# WX0_008_958DL.net
KiCad netlist of a schematic drawn in Altium Designer
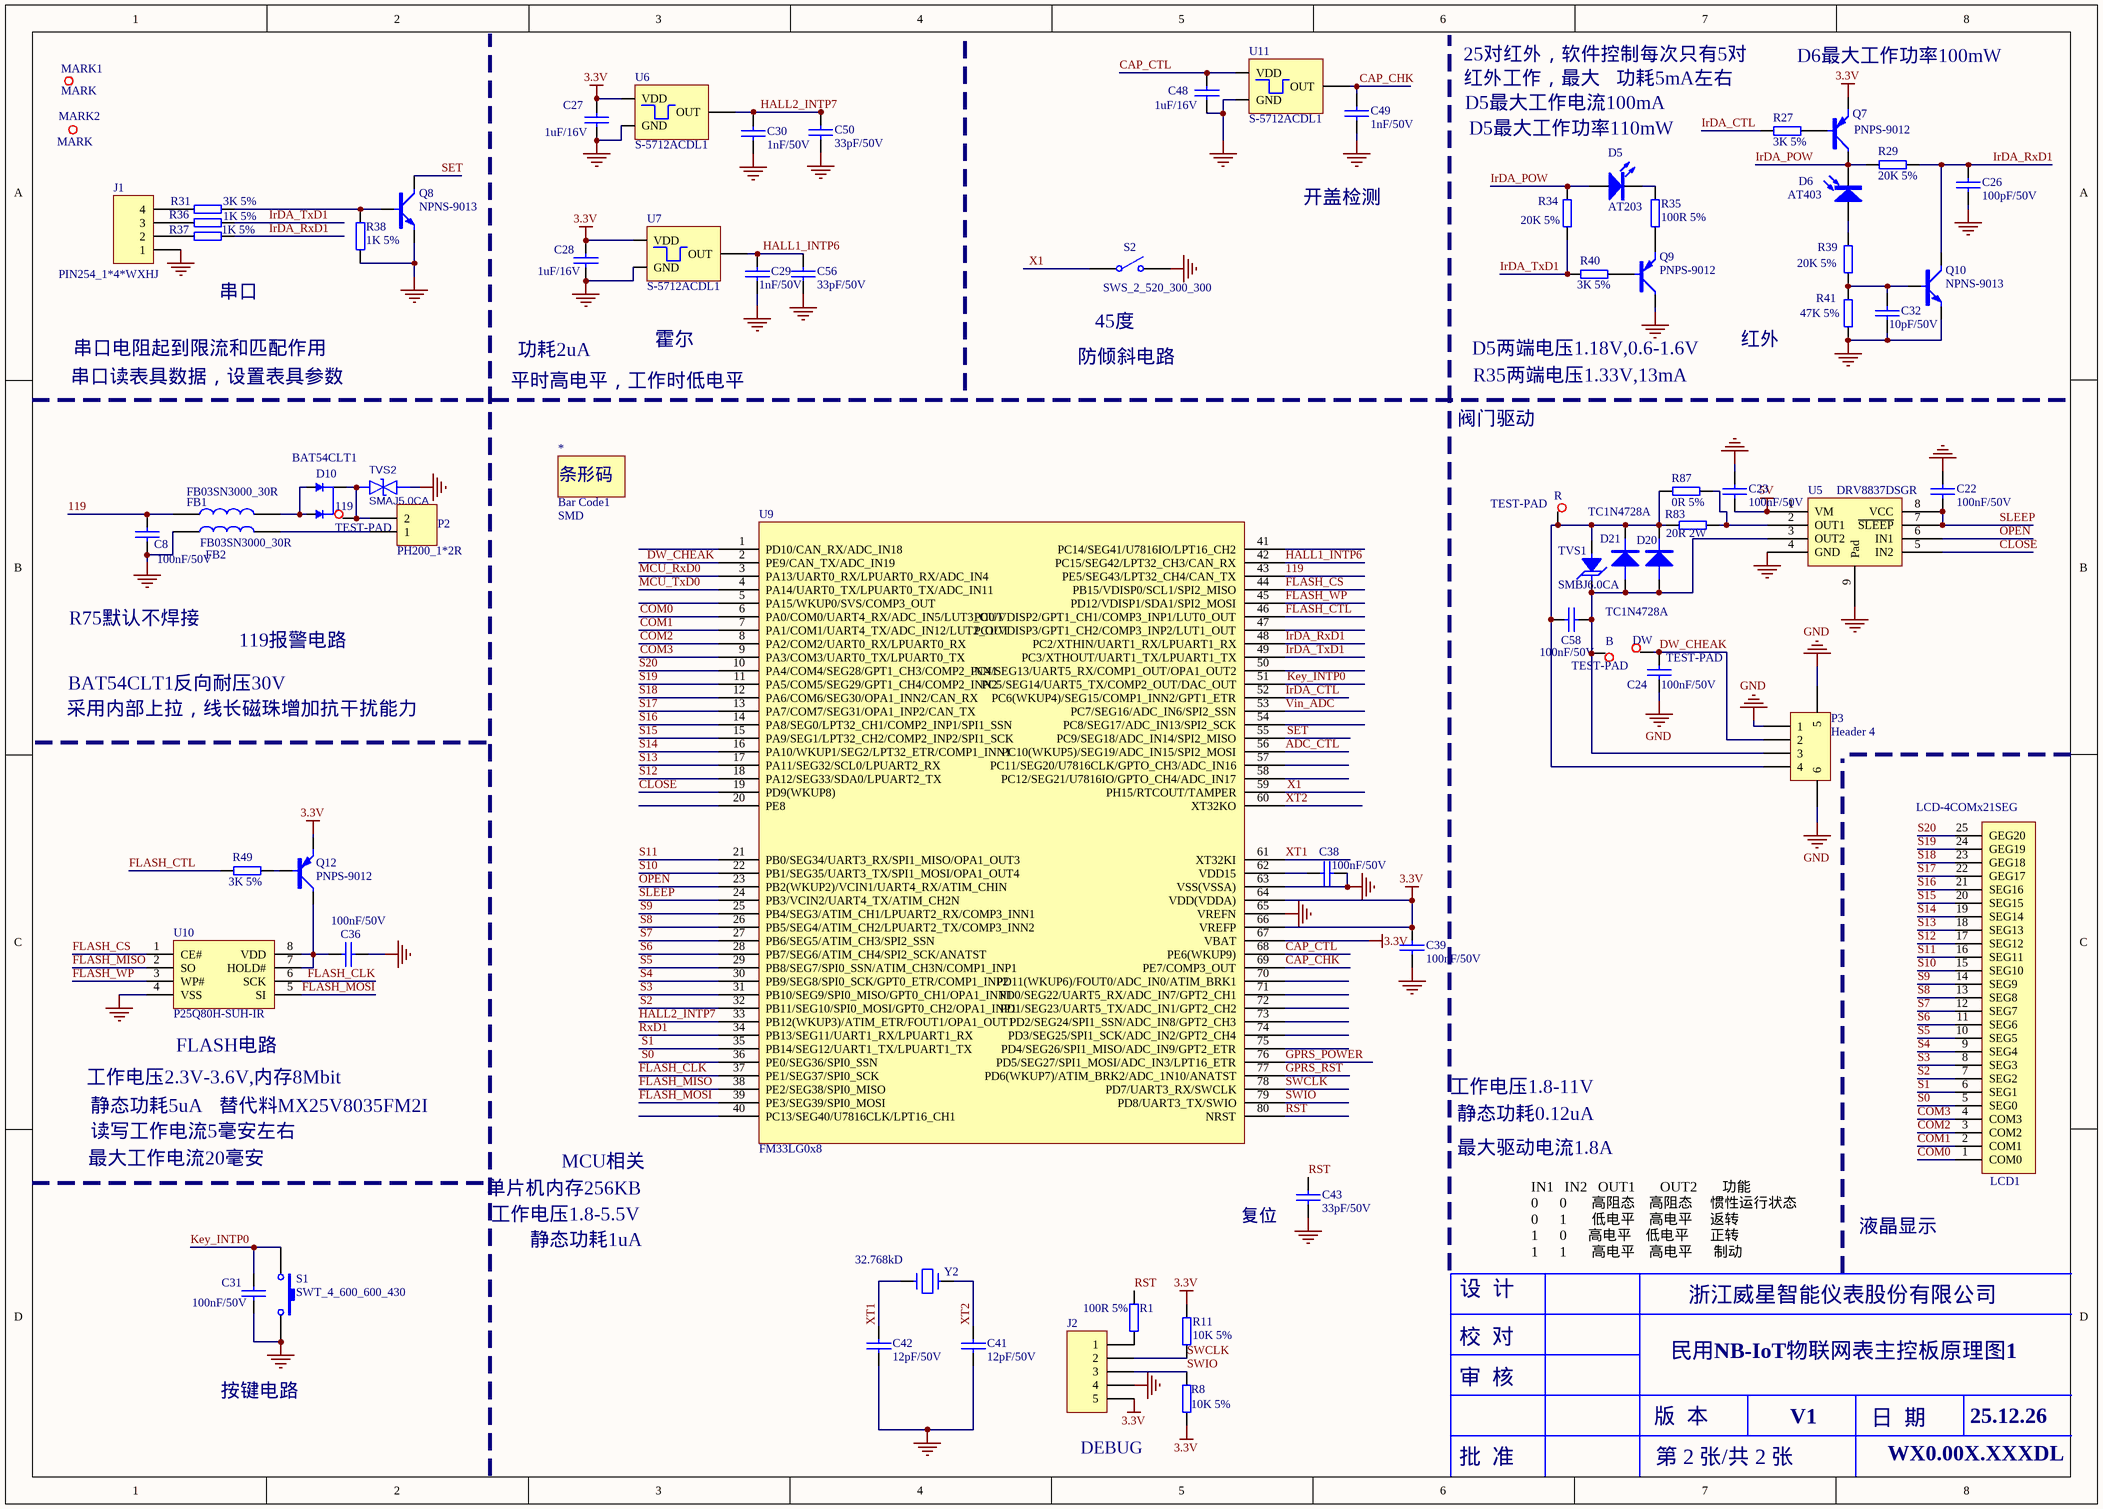
[diagram p0: WX0.008.958DL.SchDoc]

(export (version "E")
  (design (tool "Eeschema 10.0.6"))
  (components
    (comp (ref "*")
      (value "Bar Code1")
      (footprint "Bar Code1")
      (description "条形码 ,填充，无需焊接器件")
      (fields (field (name "PART NUMBER") "AD_WXHJ_Bar Code_02") (field (name "SMD/DIP") "SMD"))
      (libsource (lib "Database_Libs2") (part "05_AD_WXHJ_Bar Code_02"))
    )
    (comp (ref "119")
      (value "TEST-PAD")
      (footprint "TEST-PAD")
      (description "单面焊盘测试点")
      (fields (field (name "PART NUMBER") "AD_WXHJ_TEST-PAD_01"))
      (libsource (lib "Database_Libs2") (part "TEST-PAD"))
    )
    (comp (ref "B")
      (value "TEST-PAD")
      (footprint "TEST-PAD")
      (description "单面焊盘测试点")
      (fields (field (name "PART NUMBER") "AD_WXHJ_TEST-PAD_01"))
      (libsource (lib "Database_Libs2") (part "TEST-PAD"))
    )
    (comp (ref "C8")
      (value "100nF/50V")
      (footprint "CAP0603")
      (description "104pF,50 V,±10%,0603,国巨,CC0603KRX7R9BB104")
      (fields (field (name "PART NUMBER") "101020103-0021"))
      (libsource (lib "Database_Libs2") (part "CC03K7R9_100N"))
    )
    (comp (ref "C22")
      (value "100nF/50V")
      (footprint "CAP0603")
      (description "104pF,50 V,±10%,0603,国巨,CC0603KRX7R9BB104")
      (fields (field (name "PART NUMBER") "101020103-0021"))
      (libsource (lib "Database_Libs2") (part "CC03K7R9_100N"))
    )
    (comp (ref "C23")
      (value "100nF/50V")
      (footprint "CAP0603")
      (description "104pF,50 V,±10%,0603,国巨,CC0603KRX7R9BB104")
      (fields (field (name "PART NUMBER") "101020103-0021"))
      (libsource (lib "Database_Libs2") (part "CC03K7R9_100N"))
    )
    (comp (ref "C24")
      (value "100nF/50V")
      (footprint "CAP0603")
      (description "104pF,50 V,±10%,0603,国巨,CC0603KRX7R9BB104")
      (fields (field (name "PART NUMBER") "101020103-0021"))
      (libsource (lib "Database_Libs2") (part "CC03K7R9_100N"))
    )
    (comp (ref "C26")
      (value "100pF/50V")
      (footprint "CAP0603")
      (description "101pf,50 V,±5%,0603,国巨,CC0603JRNP09BN101")
      (fields (field (name "PART NUMBER") "101020103-0010"))
      (libsource (lib "Database_Libs2") (part "CC03JPO9_101P"))
    )
    (comp (ref "C27")
      (value "1uF/16V")
      (footprint "CAP0603")
      (description "105pF,16 V,±10%,0603,国巨,CC0603KRX7R7BB105")
      (fields (field (name "PART NUMBER") "101020103-0003"))
      (libsource (lib "Database_Libs2") (part "CC03K7R7_1U"))
    )
    (comp (ref "C28")
      (value "1uF/16V")
      (footprint "CAP0603")
      (description "105pF,16 V,±10%,0603,国巨,CC0603KRX7R7BB105")
      (fields (field (name "PART NUMBER") "101020103-0003"))
      (libsource (lib "Database_Libs2") (part "CC03K7R7_1U"))
    )
    (comp (ref "C29")
      (value "1nF/50V")
      (footprint "CAP0603")
      (description "102pF,50 V,±10%,0603,国巨,CC0603KRX7R9BB102")
      (fields (field (name "PART NUMBER") "101020103-0022"))
      (libsource (lib "Database_Libs2") (part "CC03K7R9_1N"))
    )
    (comp (ref "C30")
      (value "1nF/50V")
      (footprint "CAP0603")
      (description "102pF,50 V,±10%,0603,国巨,CC0603KRX7R9BB102")
      (fields (field (name "PART NUMBER") "101020103-0022"))
      (libsource (lib "Database_Libs2") (part "CC03K7R9_1N"))
    )
    (comp (ref "C31")
      (value "100nF/50V")
      (footprint "CAP0603")
      (description "104pF,50 V,±10%,0603,国巨,CC0603KRX7R9BB104")
      (fields (field (name "PART NUMBER") "101020103-0021"))
      (libsource (lib "Database_Libs2") (part "CC03K7R9_100N"))
    )
    (comp (ref "C32")
      (value "10pF/50V")
      (footprint "CAP0603")
      (description "10pF,50 V,±5%,0603,X7R,国巨,CC0603JRNPO9BN100")
      (fields (field (name "PART NUMBER") "101020103-0014"))
      (libsource (lib "Database_Libs2") (part "CC03JPO9_10P"))
    )
    (comp (ref "C36")
      (value "100nF/50V")
      (footprint "CAP0603")
      (description "104pF,50 V,±10%,0603,国巨,CC0603KRX7R9BB104")
      (fields (field (name "PART NUMBER") "101020103-0021"))
      (libsource (lib "Database_Libs2") (part "CC03K7R9_100N"))
    )
    (comp (ref "C38")
      (value "100nF/50V")
      (footprint "CAP0603")
      (description "104pF,50 V,±10%,0603,国巨,CC0603KRX7R9BB104")
      (fields (field (name "PART NUMBER") "101020103-0021"))
      (libsource (lib "Database_Libs2") (part "CC03K7R9_100N"))
    )
    (comp (ref "C39")
      (value "100nF/50V")
      (footprint "CAP0603")
      (description "104pF,50 V,±10%,0603,国巨,CC0603KRX7R9BB104")
      (fields (field (name "PART NUMBER") "101020103-0021"))
      (libsource (lib "Database_Libs2") (part "CC03K7R9_100N"))
    )
    (comp (ref "C41")
      (value "12pF/50V")
      (footprint "CAP0603")
      (description "12P,50 V,±5%,0603,国巨,CC0603JRNPO9BN12")
      (fields (field (name "PART NUMBER") "101020103-0005"))
      (libsource (lib "Database_Libs2") (part "CC03JPO9_12P"))
    )
    (comp (ref "C42")
      (value "12pF/50V")
      (footprint "CAP0603")
      (description "12P,50 V,±5%,0603,国巨,CC0603JRNPO9BN12")
      (fields (field (name "PART NUMBER") "101020103-0005"))
      (libsource (lib "Database_Libs2") (part "CC03JPO9_12P"))
    )
    (comp (ref "C43")
      (value "33pF/50V")
      (footprint "CAP0603")
      (description "33pF,50 V,±10%,0603,国巨,CC0603KRNPO9BN33")
      (fields (field (name "PART NUMBER") "101020103-0027"))
      (libsource (lib "Database_Libs2") (part "CC03KPO9_33P"))
    )
    (comp (ref "C48")
      (value "1uF/16V")
      (footprint "CAP0603")
      (description "105pF,16 V,±10%,0603,国巨,CC0603KRX7R7BB105")
      (fields (field (name "PART NUMBER") "101020103-0003"))
      (libsource (lib "Database_Libs2") (part "CC03K7R7_1U"))
    )
    (comp (ref "C49")
      (value "1nF/50V")
      (footprint "CAP0603")
      (description "102pF,50 V,±10%,0603,国巨,CC0603KRX7R9BB102")
      (fields (field (name "PART NUMBER") "101020103-0022"))
      (libsource (lib "Database_Libs2") (part "CC03K7R9_1N"))
    )
    (comp (ref "C50")
      (value "33pF/50V")
      (footprint "CAP0603")
      (description "33pF,50 V,±10%,0603,国巨,CC0603KRNPO9BN33")
      (fields (field (name "PART NUMBER") "101020103-0027"))
      (libsource (lib "Database_Libs2") (part "CC03KPO9_33P"))
    )
    (comp (ref "C56")
      (value "33pF/50V")
      (footprint "CAP0603")
      (description "33pF,50 V,±10%,0603,国巨,CC0603KRNPO9BN33")
      (fields (field (name "PART NUMBER") "101020103-0027"))
      (libsource (lib "Database_Libs2") (part "CC03KPO9_33P"))
    )
    (comp (ref "C58")
      (value "100nF/50V")
      (footprint "CAP0603")
      (description "104pF,50 V,±10%,0603,国巨,CC0603KRX7R9BB104")
      (fields (field (name "PART NUMBER") "101020103-0021"))
      (libsource (lib "Database_Libs2") (part "CC03K7R9_100N"))
    )
    (comp (ref "D5")
      (value "AT203")
      (footprint "IR_254_532_300")
      (description "DIP-2,φ3,插件,红光,上海品观电子有限公司/可得,AT203")
      (fields (field (name "PART NUMBER") "101040102-0010"))
      (libsource (lib "Database_Libs2") (part "01_AT203"))
    )
    (comp (ref "D6")
      (value "AT403")
      (footprint "IR_254_532_300")
      (description "DIP-2,φ3,插件,红光,上海品观电子有限公司/可得,AT403-PD-01")
      (fields (field (name "PART NUMBER") "101040102-0011"))
      (libsource (lib "Database_Libs2") (part "01_AT403"))
    )
    (comp (ref "D10")
      (value "BAT54CLT1")
      (footprint "SOT-23")
      (description "BAT54CLT1，SOT23-3,SOT23-3,0.2 A,0.8 V,30 V,安森美,BAT54CLT1")
      (fields (field (name "PART NUMBER") "101040101-0038"))
      (libsource (lib "Database_Libs2") (part "02_BAT54CLT1"))
    )
    (comp (ref "D20")
      (value "TC1N4728A")
      (footprint "SOD-123FL")
      (description "4148,4148,0.2 A,1 V,100 V,先科,LL4148")
      (fields (field (name "PART NUMBER") "101040101-0005"))
      (libsource (lib "Database_Libs2") (part "02_LL4148"))
    )
    (comp (ref "D21")
      (value "TC1N4728A")
      (footprint "SOD-123FL")
      (description "4148,4148,0.2 A,1 V,100 V,先科,LL4148")
      (fields (field (name "PART NUMBER") "101040101-0005"))
      (libsource (lib "Database_Libs2") (part "02_LL4148"))
    )
    (comp (ref "DW")
      (value "TEST-PAD")
      (footprint "TEST-PAD")
      (description "单面焊盘测试点")
      (fields (field (name "PART NUMBER") "AD_WXHJ_TEST-PAD_01"))
      (libsource (lib "Database_Libs2") (part "TEST-PAD"))
    )
    (comp (ref "FB1")
      (value "FB03SN3000_30R")
      (footprint "IND0603")
      (description "chilisin(奇力新),0603,30Ω ±25% @100MHz,150 V,125 ℃,PBY160808T-300Y-N,-55 ℃,不含铅,,,圆盘,30Ω ±25% @100MHz")
      (fields (field (name "PART NUMBER") "109010101-0003"))
      (libsource (lib "Database_Libs2") (part "06_FB03SN3000_30R"))
    )
    (comp (ref "FB2")
      (value "FB03SN3000_30R")
      (footprint "IND0603")
      (description "chilisin(奇力新),0603,30Ω ±25% @100MHz,150 V,125 ℃,PBY160808T-300Y-N,-55 ℃,不含铅,,,圆盘,30Ω ±25% @100MHz")
      (fields (field (name "PART NUMBER") "109010101-0003"))
      (libsource (lib "Database_Libs2") (part "06_FB03SN3000_30R"))
    )
    (comp (ref "J1")
      (value "PIN254_1*4*WXHJ")
      (footprint "PIN254_1*4*WXHJ")
      (description "1*4 ，Φ1.0 ，2.54mm，直脚,无需焊接器件")
      (fields (field (name "PART NUMBER") "AD_WXHJ_PinHeader_01"))
      (libsource (lib "Database_Libs2") (part "PIN254_1*4*WXHJ"))
    )
    (comp (ref "J2")
      (value "PIN254_1*5*WXHJ")
      (footprint "PIN254_1*5*WXHJ")
      (description "1*5 ，Φ1.0 ，2.54mm，直脚,无需焊接器件")
      (fields (field (name "PART NUMBER") "AD_WXHJ_PinHeader_02"))
      (libsource (lib "Database_Libs2") (part "PIN254_1*5*WXHJ"))
    )
    (comp (ref "LCD1")
      (value "GVH21861A-HPP")
      (footprint "WX0.008.919PCB-4.1 YUANJIAN:LCD_GVH21861A-HPP")
      (fields (field (name "PART NUMBER") "1010801-0028") (field (name "SMD/DIP") "LCD-4COMx21SEG"))
      (libsource (lib "Database_Libs2") (part "03_LCD_GVH21861A-HPP"))
    )
    (comp (ref "MARK1")
      (value "MARK")
      (footprint "MARK")
      (description "MARK点")
      (fields (field (name "PART NUMBER") "AD_WXHJ_MARK_01"))
      (libsource (lib "Database_Libs2") (part "MARK"))
    )
    (comp (ref "MARK2")
      (value "MARK")
      (footprint "MARK")
      (description "MARK点")
      (fields (field (name "PART NUMBER") "AD_WXHJ_MARK_01"))
      (libsource (lib "Database_Libs2") (part "MARK"))
    )
    (comp (ref "P2")
      (value "PH200_1*2R")
      (footprint "SMT2-2.0")
      (description "2.0-2AW,直插弯座，2PIN，脚间距2mm，带防翘起,公头,单排,2.0-2AW;直插弯座，2PIN,脚间距2mm，带防翘起")
      (fields (field (name "PART NUMBER") "1010902-0105"))
      (libsource (lib "Database_Libs2") (part "PH200_1*2R"))
    )
    (comp (ref "P3")
      (value "Header 4")
      (footprint "WX0.009.048PCB-4.1:SMT-1.25-4")
      (description "Header, 4-Pin")
      (fields (field (name "PUBLISHER") "Altium Limited"))
      (libsource (lib "WX0.000.514") (part "Header 4"))
    )
    (comp (ref "Q7")
      (value "PNPS-9012")
      (footprint "SOT-23")
      (description "9012,PNP,SOT-23,JCET;长电,S9012")
      (fields (field (name "PART NUMBER") "101040201-0001"))
      (libsource (lib "Database_Libs2") (part "03_PNPS-9012"))
    )
    (comp (ref "Q8")
      (value "NPNS-9013")
      (footprint "SOT-23")
      (description "9013,NPN,SOT-23,长电,S9013")
      (fields (field (name "PART NUMBER") "101040201-0002"))
      (libsource (lib "Database_Libs2") (part "03_NPNS-9013"))
    )
    (comp (ref "Q9")
      (value "PNPS-9012")
      (footprint "SOT-23")
      (description "9012,PNP,SOT-23,JCET;长电,S9012")
      (fields (field (name "PART NUMBER") "101040201-0001"))
      (libsource (lib "Database_Libs2") (part "03_PNPS-9012"))
    )
    (comp (ref "Q10")
      (value "NPNS-9013")
      (footprint "SOT-23")
      (description "9013,NPN,SOT-23,长电,S9013")
      (fields (field (name "PART NUMBER") "101040201-0002"))
      (libsource (lib "Database_Libs2") (part "03_NPNS-9013"))
    )
    (comp (ref "Q12")
      (value "PNPS-9012")
      (footprint "SOT-23")
      (description "9012,PNP,SOT-23,JCET;长电,S9012")
      (fields (field (name "PART NUMBER") "101040201-0001"))
      (libsource (lib "Database_Libs2") (part "03_PNPS-9012"))
    )
    (comp (ref "R")
      (value "TEST-PAD")
      (footprint "TEST-PAD")
      (description "单面焊盘测试点")
      (fields (field (name "PART NUMBER") "AD_WXHJ_TEST-PAD_01"))
      (libsource (lib "Database_Libs2") (part "TEST-PAD"))
    )
    (comp (ref "R1")
      (value "100R 5%")
      (footprint "RES0603")
      (description "100R,±5%,1/10W,0603,国巨,RC0603JR-07100RL")
      (fields (field (name "PART NUMBER") "101010103-0022"))
      (libsource (lib "Database_Libs2") (part "RC03J_100R"))
    )
    (comp (ref "R8")
      (value "10K 5%")
      (footprint "RES0603")
      (description "国巨,±5%,0603,,155 ℃,-55 ℃,RC0603JR-0710KL,无铅,200 ppm/℃,1/10W,,10K")
      (fields (field (name "PART NUMBER") "101010103-0003"))
      (libsource (lib "Database_Libs2") (part "RC03J_10K"))
    )
    (comp (ref "R11")
      (value "10K 5%")
      (footprint "RES0603")
      (description "国巨,±5%,0603,,155 ℃,-55 ℃,RC0603JR-0710KL,无铅,200 ppm/℃,1/10W,,10K")
      (fields (field (name "PART NUMBER") "101010103-0003"))
      (libsource (lib "Database_Libs2") (part "RC03J_10K"))
    )
    (comp (ref "R27")
      (value "3K 5%")
      (footprint "RES0603")
      (description "国巨,±5%,0603,,155 ℃,-55 ℃,RC0603JR-073KL,无铅,100 ppm/℃,1/10W,,3K")
      (fields (field (name "PART NUMBER") "101010103-0006"))
      (libsource (lib "Database_Libs2") (part "RC03J_3K"))
    )
    (comp (ref "R29")
      (value "20K 5%")
      (footprint "RES0603")
      (description "国巨,±5%,0603,,155 ℃,-55 ℃,RC0603JR-0720KL,无铅,200 ppm/℃,1/10W,,20K")
      (fields (field (name "PART NUMBER") "101010103-0004"))
      (libsource (lib "Database_Libs2") (part "RC03J_20K"))
    )
    (comp (ref "R31")
      (value "3K 5%")
      (footprint "RES0603")
      (description "国巨,±5%,0603,,155 ℃,-55 ℃,RC0603JR-073KL,无铅,100 ppm/℃,1/10W,,3K")
      (fields (field (name "PART NUMBER") "101010103-0006"))
      (libsource (lib "Database_Libs2") (part "RC03J_3K"))
    )
    (comp (ref "R34")
      (value "20K 5%")
      (footprint "RES0603")
      (description "国巨,±5%,0603,,155 ℃,-55 ℃,RC0603JR-0720KL,无铅,200 ppm/℃,1/10W,,20K")
      (fields (field (name "PART NUMBER") "101010103-0004"))
      (libsource (lib "Database_Libs2") (part "RC03J_20K"))
    )
    (comp (ref "R35")
      (value "100R 5%")
      (footprint "RES0603")
      (description "100R,±5%,1/10W,0603,国巨,RC0603JR-07100RL")
      (fields (field (name "PART NUMBER") "101010103-0022"))
      (libsource (lib "Database_Libs2") (part "RC03J_100R"))
    )
    (comp (ref "R36")
      (value "1K 5%")
      (footprint "RES0603")
      (description "1K,±5%,1/10W,0603,国巨,RC0603JR-071KL")
      (fields (field (name "PART NUMBER") "101010103-0008"))
      (libsource (lib "Database_Libs2") (part "RC03J_1K"))
    )
    (comp (ref "R37")
      (value "1K 5%")
      (footprint "RES0603")
      (description "1K,±5%,1/10W,0603,国巨,RC0603JR-071KL")
      (fields (field (name "PART NUMBER") "101010103-0008"))
      (libsource (lib "Database_Libs2") (part "RC03J_1K"))
    )
    (comp (ref "R38")
      (value "1K 5%")
      (footprint "RES0603")
      (description "1K,±5%,1/10W,0603,国巨,RC0603JR-071KL")
      (fields (field (name "PART NUMBER") "101010103-0008"))
      (libsource (lib "Database_Libs2") (part "RC03J_1K"))
    )
    (comp (ref "R39")
      (value "20K 5%")
      (footprint "RES0603")
      (description "国巨,±5%,0603,,155 ℃,-55 ℃,RC0603JR-0720KL,无铅,200 ppm/℃,1/10W,,20K")
      (fields (field (name "PART NUMBER") "101010103-0004"))
      (libsource (lib "Database_Libs2") (part "RC03J_20K"))
    )
    (comp (ref "R40")
      (value "3K 5%")
      (footprint "RES0603")
      (description "国巨,±5%,0603,,155 ℃,-55 ℃,RC0603JR-073KL,无铅,100 ppm/℃,1/10W,,3K")
      (fields (field (name "PART NUMBER") "101010103-0006"))
      (libsource (lib "Database_Libs2") (part "RC03J_3K"))
    )
    (comp (ref "R41")
      (value "47K 5%")
      (footprint "RES0603")
      (description "47K,±5%,1/10W,0603,国巨,RC0603JR-0747KL")
      (fields (field (name "PART NUMBER") "101010103-0012"))
      (libsource (lib "Database_Libs2") (part "RC03J_47K"))
    )
    (comp (ref "R49")
      (value "3K 5%")
      (footprint "RES0603")
      (description "国巨,±5%,0603,,155 ℃,-55 ℃,RC0603JR-073KL,无铅,100 ppm/℃,1/10W,,3K")
      (fields (field (name "PART NUMBER") "101010103-0006"))
      (libsource (lib "Database_Libs2") (part "RC03J_3K"))
    )
    (comp (ref "R83")
      (value "20R 2W")
      (footprint "金属膜电阻")
      (description "国巨,±5%,0603,,155 ℃,-55 ℃,RC0603JR-0722RL,无铅,200 ppm/℃,1/10W,,22欧")
      (fields (field (name "PART NUMBER") "101010103-0009"))
      (libsource (lib "Database_Libs2") (part "RC03J_22R"))
    )
    (comp (ref "R87")
      (value "0R 5%")
      (footprint "RES1206")
      (description "0Ω,±5%,1/4W,1206,国巨,RC1206JR-070RL")
      (fields (field (name "PART NUMBER") "101010101-0013"))
      (libsource (lib "Database_Libs2") (part "RC06J_0R"))
    )
    (comp (ref "S1")
      (value "SWT_4_600_600_430")
      (footprint "SWT_4_600_600")
      (description "TS-1102,机械轻触,6*6*4.3直插,6*6*4.3直插,乐清市羽欧电子")
      (fields (field (name "PART NUMBER") "1011001-0027"))
      (libsource (lib "Database_Libs2") (part "07_SWT_4_600_600_430"))
    )
    (comp (ref "S2")
      (value "SWS_2_520_300_300")
      (footprint "Discrete_WX:SWS_2_520_300")
      (description "CSX-SEN-645B,垂直45°开关转换,3*5.2mm,360°任意方位倾斜检测,深圳市成晟科技有限公司")
      (fields (field (name "PART NUMBER") "1011001-0051"))
      (libsource (lib "Database_Libs2") (part "07_SWS_2_520_300_300"))
    )
    (comp (ref "TVS1")
      (value "SMBJ6.0CA")
      (footprint "DO-214AA")
      (description "SMBJ6.0CA,DO-214AA,10.3 V,6.0 V,600 W,58.3 A,800 uA,上海君耀电子有限公司,SMBJ6.0CA")
      (fields (field (name "PART NUMBER") "101040101-0024"))
      (libsource (lib "Database_Libs2") (part "05_SMBJ6.0CA"))
    )
    (comp (ref "TVS2")
      (value "SMAJ5.0CA")
      (footprint "SMAJ5.0CA")
      (fields (field (name "BOM_SUPPLIER PART") "C693487") (field (name "CONTRIBUTOR") "LCSC"))
      (libsource (lib "Discrete_WX") (part "SMAJ5.0CA_C693487"))
    )
    (comp (ref "U5")
      (value "DRV8837DSGR")
      (footprint "S-PWSON-N8")
      (description "DRV8837DSGR,S-PWSON-N8,TI,DRV8837DSGR")
      (fields (field (name "PART NUMBER") "101050101-0060"))
      (libsource (lib "Database_Libs2") (part "07_DRV8837DSGR"))
    )
    (comp (ref "U6")
      (value "S-5712ACDL1")
      (footprint "SOT-23")
      (description "S-5712ACDL1,SOT23-3,3.5 V,1.6 V,2 uA,精工电子,S-5712ACDL1")
      (fields (field (name "PART NUMBER") "1010504-0002"))
      (libsource (lib "Database_Libs2") (part "01_S-5712ACDL1"))
    )
    (comp (ref "U7")
      (value "S-5712ACDL1")
      (footprint "SOT-23")
      (description "S-5712ACDL1,SOT23-3,3.5 V,1.6 V,2 uA,精工电子,S-5712ACDL1")
      (fields (field (name "PART NUMBER") "1010504-0002"))
      (libsource (lib "Database_Libs2") (part "01_S-5712ACDL1"))
    )
    (comp (ref "U9")
      (value "FM33LG0x8")
      (footprint "Chip_WX:LQFP80")
      (libsource (lib "FM_MCU") (part "FM33LG0x8"))
    )
    (comp (ref "U10")
      (value "P25Q80H-SUH-IR")
      (footprint "SOP-8L-200MIL")
      (description "P25Q80H-SUH-IR,SOP8208mil,普冉半导体（上海）股份有限公司,P25Q80H-SUH-IR")
      (fields (field (name "PART NUMBER") "101050101-0218"))
      (libsource (lib "Database_Libs2") (part "04_GD25VQ80CSIG"))
    )
    (comp (ref "U11")
      (value "S-5712ACDL1")
      (footprint "SOT-23")
      (description "S-5712ACDL1,SOT23-3,3.5 V,1.6 V,2 uA,精工电子,S-5712ACDL1")
      (fields (field (name "PART NUMBER") "1010504-0002"))
      (libsource (lib "Database_Libs2") (part "01_S-5712ACDL1"))
    )
    (comp (ref "Y2")
      (value "32.768kD")
      (footprint "SMD-3215_2P")
      (fields (field (name "PART NUMBER") "1010601-0020"))
      (libsource (lib "Database_Libs2") (part "04_XTALSG12MD_32.768kD"))
    )
  )
  (nets
    (net (code "1") (name "/119") (class "Default")
      (node (ref "C8") (pin "1") (pinfunction "1_1") (pintype "passive"))
      (node (ref "FB1") (pin "1") (pinfunction "1_1") (pintype "passive"))
      (node (ref "U9") (pin "43") (pinfunction "PE5/SEG43/LPT32_CH4/CAN_TX_43") (pintype "passive"))
    )
    (net (code "2") (name "/ADC_CTL") (class "Default")
      (node (ref "U9") (pin "56") (pinfunction "PC10(WKUP5)/SEG19/ADC_IN15/SPI2_MOSI_56") (pintype "passive"))
    )
    (net (code "3") (name "/CAP_CHK") (class "Default")
      (node (ref "C49") (pin "1") (pinfunction "1_1") (pintype "passive"))
      (node (ref "U11") (pin "2") (pinfunction "OUT_2") (pintype "passive"))
      (node (ref "U9") (pin "69") (pinfunction "PE7/COMP3_OUT_69") (pintype "passive"))
    )
    (net (code "4") (name "/CAP_CTL") (class "Default")
      (node (ref "C48") (pin "1") (pinfunction "1_1") (pintype "passive"))
      (node (ref "U11") (pin "1") (pinfunction "VDD_1") (pintype "passive"))
      (node (ref "U9") (pin "68") (pinfunction "PE6(WKUP9)_68") (pintype "passive"))
    )
    (net (code "5") (name "/CLOSE") (class "Default")
      (node (ref "U5") (pin "5") (pinfunction "IN2_5") (pintype "passive"))
      (node (ref "U9") (pin "19") (pinfunction "PD9(WKUP8)_19") (pintype "passive"))
    )
    (net (code "6") (name "/COM0") (class "Default")
      (node (ref "LCD1") (pin "1") (pinfunction "COM0_1") (pintype "passive"))
      (node (ref "U9") (pin "6") (pinfunction "PA0/COM0/UART4_RX/ADC_IN5/LUT3_OUT_6") (pintype "passive"))
    )
    (net (code "7") (name "/COM1") (class "Default")
      (node (ref "LCD1") (pin "2") (pinfunction "COM1_2") (pintype "passive"))
      (node (ref "U9") (pin "7") (pinfunction "PA1/COM1/UART4_TX/ADC_IN12/LUT2_OUT_7") (pintype "passive"))
    )
    (net (code "8") (name "/COM2") (class "Default")
      (node (ref "LCD1") (pin "3") (pinfunction "COM2_3") (pintype "passive"))
      (node (ref "U9") (pin "8") (pinfunction "PA2/COM2/UART0_RX/LPUART0_RX_8") (pintype "passive"))
    )
    (net (code "9") (name "/COM3") (class "Default")
      (node (ref "LCD1") (pin "4") (pinfunction "COM3_4") (pintype "passive"))
      (node (ref "U9") (pin "9") (pinfunction "PA3/COM3/UART0_TX/LPUART0_TX_9") (pintype "passive"))
    )
    (net (code "10") (name "/DW_CHEAK") (class "Default")
      (node (ref "C24") (pin "1") (pinfunction "1_1") (pintype "passive"))
      (node (ref "DW") (pin "1") (pinfunction "1_1") (pintype "passive"))
      (node (ref "P3") (pin "2") (pinfunction "2_2") (pintype "passive"))
      (node (ref "U9") (pin "2") (pinfunction "PE9/CAN_TX/ADC_IN19_2") (pintype "passive"))
    )
    (net (code "11") (name "/FLASH_CLK") (class "Default")
      (node (ref "U10") (pin "6") (pinfunction "SCK_6") (pintype "passive"))
      (node (ref "U9") (pin "37") (pinfunction "PE1/SEG37/SPI0_SCK_37") (pintype "passive"))
    )
    (net (code "12") (name "/FLASH_CS") (class "Default")
      (node (ref "U10") (pin "1") (pinfunction "CE#_1") (pintype "passive"))
      (node (ref "U9") (pin "44") (pinfunction "PB15/VDISP0/SCL1/SPI2_MISO_44") (pintype "passive"))
    )
    (net (code "13") (name "/FLASH_CTL") (class "Default")
      (node (ref "R49") (pin "1") (pinfunction "1_1") (pintype "passive"))
      (node (ref "U9") (pin "46") (pinfunction "PC0/VDISP2/GPT1_CH1/COMP3_INP1/LUT0_OUT_46") (pintype "passive"))
    )
    (net (code "14") (name "/FLASH_MISO") (class "Default")
      (node (ref "U10") (pin "2") (pinfunction "SO_2") (pintype "passive"))
      (node (ref "U9") (pin "38") (pinfunction "PE2/SEG38/SPI0_MISO_38") (pintype "passive"))
    )
    (net (code "15") (name "/FLASH_MOSI") (class "Default")
      (node (ref "U10") (pin "5") (pinfunction "SI_5") (pintype "passive"))
      (node (ref "U9") (pin "39") (pinfunction "PE3/SEG39/SPI0_MOSI_39") (pintype "passive"))
    )
    (net (code "16") (name "/FLASH_WP") (class "Default")
      (node (ref "U10") (pin "3") (pinfunction "WP#_3") (pintype "passive"))
      (node (ref "U9") (pin "45") (pinfunction "PD12/VDISP1/SDA1/SPI2_MOSI_45") (pintype "passive"))
    )
    (net (code "17") (name "/GPRS_POWER") (class "Default")
      (node (ref "U9") (pin "76") (pinfunction "PD5/SEG27/SPI1_MOSI/ADC_IN3/LPT16_ETR_76") (pintype "passive"))
    )
    (net (code "18") (name "/GPRS_RST") (class "Default")
      (node (ref "U9") (pin "77") (pinfunction "PD6(WKUP7)/ATIM_BRK2/ADC_1N10/ANATST_77") (pintype "passive"))
    )
    (net (code "19") (name "/HALL1_INTP6") (class "Default")
      (node (ref "C29") (pin "1") (pinfunction "1_1") (pintype "passive"))
      (node (ref "C56") (pin "1") (pinfunction "1_1") (pintype "passive"))
      (node (ref "U7") (pin "2") (pinfunction "OUT_2") (pintype "passive"))
      (node (ref "U9") (pin "42") (pinfunction "PC15/SEG42/LPT32_CH3/CAN_RX_42") (pintype "passive"))
    )
    (net (code "20") (name "/HALL2_INTP7") (class "Default")
      (node (ref "C30") (pin "1") (pinfunction "1_1") (pintype "passive"))
      (node (ref "C50") (pin "1") (pinfunction "1_1") (pintype "passive"))
      (node (ref "U6") (pin "2") (pinfunction "OUT_2") (pintype "passive"))
      (node (ref "U9") (pin "33") (pinfunction "PB12(WKUP3)/ATIM_ETR/FOUT1/OPA1_OUT1_33") (pintype "passive"))
    )
    (net (code "21") (name "/IrDA_CTL") (class "Default")
      (node (ref "R27") (pin "1") (pinfunction "1_1") (pintype "passive"))
      (node (ref "U9") (pin "52") (pinfunction "PC6(WKUP4)/SEG15/COMP1_INN2/GPT1_ETR_52") (pintype "passive"))
    )
    (net (code "22") (name "/IrDA_POW") (class "Default")
      (node (ref "D5") (pin "1") (pinfunction "A_1") (pintype "passive"))
      (node (ref "D6") (pin "2") (pinfunction "K_2") (pintype "passive"))
      (node (ref "Q7") (pin "3") (pinfunction "C_3") (pintype "passive"))
      (node (ref "R29") (pin "1") (pinfunction "1_1") (pintype "passive"))
      (node (ref "R34") (pin "2") (pinfunction "2_2") (pintype "passive"))
    )
    (net (code "23") (name "/IrDA_RxD1") (class "Default")
      (node (ref "C26") (pin "1") (pinfunction "1_1") (pintype "passive"))
      (node (ref "Q10") (pin "3") (pinfunction "C_3") (pintype "passive"))
      (node (ref "R29") (pin "2") (pinfunction "2_2") (pintype "passive"))
      (node (ref "R37") (pin "2") (pinfunction "2_2") (pintype "passive"))
      (node (ref "U9") (pin "48") (pinfunction "PC2/XTHIN/UART1_RX/LPUART1_RX_48") (pintype "passive"))
    )
    (net (code "24") (name "/IrDA_TxD1") (class "Default")
      (node (ref "R34") (pin "1") (pinfunction "1_1") (pintype "passive"))
      (node (ref "R36") (pin "2") (pinfunction "2_2") (pintype "passive"))
      (node (ref "R40") (pin "1") (pinfunction "1_1") (pintype "passive"))
      (node (ref "U9") (pin "49") (pinfunction "PC3/XTHOUT/UART1_TX/LPUART1_TX_49") (pintype "passive"))
    )
    (net (code "25") (name "/Key_INTP0") (class "Default")
      (node (ref "C31") (pin "1") (pinfunction "1_1") (pintype "passive"))
      (node (ref "S1") (pin "1") (pinfunction "1_1") (pintype "passive"))
      (node (ref "U9") (pin "51") (pinfunction "PC5/SEG14/UART5_TX/COMP2_OUT/DAC_OUT_51") (pintype "passive"))
    )
    (net (code "26") (name "/MCU_RxD0") (class "Default")
      (node (ref "U9") (pin "3") (pinfunction "PA13/UART0_RX/LPUART0_RX/ADC_IN4_3") (pintype "passive"))
    )
    (net (code "27") (name "/MCU_TxD0") (class "Default")
      (node (ref "U9") (pin "4") (pinfunction "PA14/UART0_TX/LPUART0_TX/ADC_IN11_4") (pintype "passive"))
    )
    (net (code "28") (name "/OPEN") (class "Default")
      (node (ref "U5") (pin "6") (pinfunction "IN1_6") (pintype "passive"))
      (node (ref "U9") (pin "23") (pinfunction "PB2(WKUP2)/VCIN1/UART4_RX/ATIM_CHIN_23") (pintype "passive"))
    )
    (net (code "29") (name "/RST") (class "Default")
      (node (ref "C43") (pin "1") (pinfunction "1_1") (pintype "passive"))
      (node (ref "R1") (pin "1") (pinfunction "1_1") (pintype "passive"))
      (node (ref "U9") (pin "80") (pinfunction "NRST_80") (pintype "passive"))
    )
    (net (code "30") (name "/RxD1") (class "Default")
      (node (ref "U9") (pin "34") (pinfunction "PB13/SEG11/UART1_RX/LPUART1_RX_34") (pintype "passive"))
    )
    (net (code "31") (name "/S0") (class "Default")
      (node (ref "LCD1") (pin "5") (pinfunction "SEG0_5") (pintype "passive"))
      (node (ref "U9") (pin "36") (pinfunction "PE0/SEG36/SPI0_SSN_36") (pintype "passive"))
    )
    (net (code "32") (name "/S1") (class "Default")
      (node (ref "LCD1") (pin "6") (pinfunction "SEG1_6") (pintype "passive"))
      (node (ref "U9") (pin "35") (pinfunction "PB14/SEG12/UART1_TX/LPUART1_TX_35") (pintype "passive"))
    )
    (net (code "33") (name "/S2") (class "Default")
      (node (ref "LCD1") (pin "7") (pinfunction "SEG2_7") (pintype "passive"))
      (node (ref "U9") (pin "32") (pinfunction "PB11/SEG10/SPI0_MOSI/GPT0_CH2/OPA1_INP1_32") (pintype "passive"))
    )
    (net (code "34") (name "/S3") (class "Default")
      (node (ref "LCD1") (pin "8") (pinfunction "SEG3_8") (pintype "passive"))
      (node (ref "U9") (pin "31") (pinfunction "PB10/SEG9/SPI0_MISO/GPT0_CH1/OPA1_INN1_31") (pintype "passive"))
    )
    (net (code "35") (name "/S4") (class "Default")
      (node (ref "LCD1") (pin "9") (pinfunction "SEG4_9") (pintype "passive"))
      (node (ref "U9") (pin "30") (pinfunction "PB9/SEG8/SPI0_SCK/GPT0_ETR/COMP1_INP2_30") (pintype "passive"))
    )
    (net (code "36") (name "/S5") (class "Default")
      (node (ref "LCD1") (pin "10") (pinfunction "SEG5_10") (pintype "passive"))
      (node (ref "U9") (pin "29") (pinfunction "PB8/SEG7/SPI0_SSN/ATIM_CH3N/COMP1_INP1_29") (pintype "passive"))
    )
    (net (code "37") (name "/S6") (class "Default")
      (node (ref "LCD1") (pin "11") (pinfunction "SEG6_11") (pintype "passive"))
      (node (ref "U9") (pin "28") (pinfunction "PB7/SEG6/ATIM_CH4/SPI2_SCK/ANATST_28") (pintype "passive"))
    )
    (net (code "38") (name "/S7") (class "Default")
      (node (ref "LCD1") (pin "12") (pinfunction "SEG7_12") (pintype "passive"))
      (node (ref "U9") (pin "27") (pinfunction "PB6/SEG5/ATIM_CH3/SPI2_SSN_27") (pintype "passive"))
    )
    (net (code "39") (name "/S8") (class "Default")
      (node (ref "LCD1") (pin "13") (pinfunction "SEG8_13") (pintype "passive"))
      (node (ref "U9") (pin "26") (pinfunction "PB5/SEG4/ATIM_CH2/LPUART2_TX/COMP3_INN2_26") (pintype "passive"))
    )
    (net (code "40") (name "/S9") (class "Default")
      (node (ref "LCD1") (pin "14") (pinfunction "SEG9_14") (pintype "passive"))
      (node (ref "U9") (pin "25") (pinfunction "PB4/SEG3/ATIM_CH1/LPUART2_RX/COMP3_INN1_25") (pintype "passive"))
    )
    (net (code "41") (name "/S10") (class "Default")
      (node (ref "LCD1") (pin "15") (pinfunction "SEG10_15") (pintype "passive"))
      (node (ref "U9") (pin "22") (pinfunction "PB1/SEG35/UART3_TX/SPI1_MOSI/OPA1_OUT4_22") (pintype "passive"))
    )
    (net (code "42") (name "/S11") (class "Default")
      (node (ref "LCD1") (pin "16") (pinfunction "SEG11_16") (pintype "passive"))
      (node (ref "U9") (pin "21") (pinfunction "PB0/SEG34/UART3_RX/SPI1_MISO/OPA1_OUT3_21") (pintype "passive"))
    )
    (net (code "43") (name "/S12") (class "Default")
      (node (ref "LCD1") (pin "17") (pinfunction "SEG12_17") (pintype "passive"))
      (node (ref "U9") (pin "18") (pinfunction "PA12/SEG33/SDA0/LPUART2_TX_18") (pintype "passive"))
    )
    (net (code "44") (name "/S13") (class "Default")
      (node (ref "LCD1") (pin "18") (pinfunction "SEG13_18") (pintype "passive"))
      (node (ref "U9") (pin "17") (pinfunction "PA11/SEG32/SCL0/LPUART2_RX_17") (pintype "passive"))
    )
    (net (code "45") (name "/S14") (class "Default")
      (node (ref "LCD1") (pin "19") (pinfunction "SEG14_19") (pintype "passive"))
      (node (ref "U9") (pin "16") (pinfunction "PA10/WKUP1/SEG2/LPT32_ETR/COMP1_INN1_16") (pintype "passive"))
    )
    (net (code "46") (name "/S15") (class "Default")
      (node (ref "LCD1") (pin "20") (pinfunction "SEG15_20") (pintype "passive"))
      (node (ref "U9") (pin "15") (pinfunction "PA9/SEG1/LPT32_CH2/COMP2_INP2/SPI1_SCK_15") (pintype "passive"))
    )
    (net (code "47") (name "/S16") (class "Default")
      (node (ref "LCD1") (pin "21") (pinfunction "SEG16_21") (pintype "passive"))
      (node (ref "U9") (pin "14") (pinfunction "PA8/SEG0/LPT32_CH1/COMP2_INP1/SPI1_SSN_14") (pintype "passive"))
    )
    (net (code "48") (name "/S17") (class "Default")
      (node (ref "LCD1") (pin "22") (pinfunction "GEG17_22") (pintype "passive"))
      (node (ref "U9") (pin "13") (pinfunction "PA7/COM7/SEG31/OPA1_INP2/CAN_TX_13") (pintype "passive"))
    )
    (net (code "49") (name "/S18") (class "Default")
      (node (ref "LCD1") (pin "23") (pinfunction "GEG18_23") (pintype "passive"))
      (node (ref "U9") (pin "12") (pinfunction "PA6/COM6/SEG30/OPA1_INN2/CAN_RX_12") (pintype "passive"))
    )
    (net (code "50") (name "/S19") (class "Default")
      (node (ref "LCD1") (pin "24") (pinfunction "GEG19_24") (pintype "passive"))
      (node (ref "U9") (pin "11") (pinfunction "PA5/COM5/SEG29/GPT1_CH4/COMP2_INN2_11") (pintype "passive"))
    )
    (net (code "51") (name "/S20") (class "Default")
      (node (ref "LCD1") (pin "25") (pinfunction "GEG20_25") (pintype "passive"))
      (node (ref "U9") (pin "10") (pinfunction "PA4/COM4/SEG28/GPT1_CH3/COMP2_INN1_10") (pintype "passive"))
    )
    (net (code "52") (name "/SET") (class "Default")
      (node (ref "Q8") (pin "3") (pinfunction "C_3") (pintype "passive"))
      (node (ref "U9") (pin "55") (pinfunction "PC9/SEG18/ADC_IN14/SPI2_MISO_55") (pintype "passive"))
    )
    (net (code "53") (name "/SLEEP") (class "Default")
      (node (ref "C22") (pin "2") (pinfunction "2_2") (pintype "passive"))
      (node (ref "U5") (pin "7") (pinfunction "~{SLEEP}_7") (pintype "passive"))
      (node (ref "U5") (pin "8") (pinfunction "VCC_8") (pintype "passive"))
      (node (ref "U9") (pin "24") (pinfunction "PB3/VCIN2/UART4_TX/ATIM_CH2N_24") (pintype "passive"))
    )
    (net (code "54") (name "/SWCLK") (class "Default")
      (node (ref "J2") (pin "2") (pinfunction "2_2") (pintype "passive"))
      (node (ref "R11") (pin "2") (pinfunction "2_2") (pintype "passive"))
      (node (ref "U9") (pin "78") (pinfunction "PD7/UART3_RX/SWCLK_78") (pintype "passive"))
    )
    (net (code "55") (name "/SWIO") (class "Default")
      (node (ref "J2") (pin "3") (pinfunction "3_3") (pintype "passive"))
      (node (ref "R8") (pin "2") (pinfunction "2_2") (pintype "passive"))
      (node (ref "U9") (pin "79") (pinfunction "PD8/UART3_TX/SWIO_79") (pintype "passive"))
    )
    (net (code "56") (name "/Vin_ADC") (class "Default")
      (node (ref "U9") (pin "53") (pinfunction "PC7/SEG16/ADC_IN6/SPI2_SSN_53") (pintype "passive"))
    )
    (net (code "57") (name "/X1") (class "Default")
      (node (ref "S2") (pin "1") (pintype "passive"))
      (node (ref "U9") (pin "59") (pinfunction "PH15/RTCOUT/TAMPER_59") (pintype "passive"))
    )
    (net (code "58") (name "/XT1") (class "Default")
      (node (ref "C42") (pin "1") (pinfunction "1_1") (pintype "passive"))
      (node (ref "U9") (pin "61") (pinfunction "XT32KI_61") (pintype "passive"))
      (node (ref "Y2") (pin "1") (pinfunction "1_1") (pintype "passive"))
    )
    (net (code "59") (name "/XT2") (class "Default")
      (node (ref "C41") (pin "2") (pinfunction "2_2") (pintype "passive"))
      (node (ref "U9") (pin "60") (pinfunction "XT32KO_60") (pintype "passive"))
      (node (ref "Y2") (pin "2") (pinfunction "2_2") (pintype "passive"))
    )
    (net (code "60") (name "3.3V") (class "Default")
      (node (ref "C27") (pin "1") (pinfunction "1_1") (pintype "passive"))
      (node (ref "C28") (pin "1") (pinfunction "1_1") (pintype "passive"))
      (node (ref "C39") (pin "2") (pinfunction "2_2") (pintype "passive"))
      (node (ref "J2") (pin "5") (pinfunction "5_5") (pintype "passive"))
      (node (ref "Q12") (pin "2") (pinfunction "E_2") (pintype "passive"))
      (node (ref "Q7") (pin "2") (pinfunction "E_2") (pintype "passive"))
      (node (ref "R11") (pin "1") (pinfunction "1_1") (pintype "passive"))
      (node (ref "R8") (pin "1") (pinfunction "1_1") (pintype "passive"))
      (node (ref "U6") (pin "1") (pinfunction "VDD_1") (pintype "passive"))
      (node (ref "U7") (pin "1") (pinfunction "VDD_1") (pintype "passive"))
      (node (ref "U9") (pin "64") (pinfunction "VDD(VDDA)_64") (pintype "passive"))
      (node (ref "U9") (pin "66") (pinfunction "VREFP_66") (pintype "passive"))
      (node (ref "U9") (pin "67") (pinfunction "VBAT_67") (pintype "passive"))
    )
    (net (code "61") (name "5V") (class "Default")
      (node (ref "C23") (pin "2") (pinfunction "2_2") (pintype "passive"))
      (node (ref "U5") (pin "1") (pinfunction "VM_1") (pintype "passive"))
    )
    (net (code "62") (name "GND") (class "Default")
      (node (ref "C22") (pin "1") (pinfunction "1_1") (pintype "passive"))
      (node (ref "C23") (pin "1") (pinfunction "1_1") (pintype "passive"))
      (node (ref "C24") (pin "2") (pinfunction "2_2") (pintype "passive"))
      (node (ref "C26") (pin "2") (pinfunction "2_2") (pintype "passive"))
      (node (ref "C27") (pin "2") (pinfunction "2_2") (pintype "passive"))
      (node (ref "C28") (pin "2") (pinfunction "2_2") (pintype "passive"))
      (node (ref "C29") (pin "2") (pinfunction "2_2") (pintype "passive"))
      (node (ref "C30") (pin "2") (pinfunction "2_2") (pintype "passive"))
      (node (ref "C31") (pin "2") (pinfunction "2_2") (pintype "passive"))
      (node (ref "C32") (pin "2") (pinfunction "2_2") (pintype "passive"))
      (node (ref "C36") (pin "2") (pinfunction "2_2") (pintype "passive"))
      (node (ref "C38") (pin "2") (pinfunction "2_2") (pintype "passive"))
      (node (ref "C39") (pin "1") (pinfunction "1_1") (pintype "passive"))
      (node (ref "C41") (pin "1") (pinfunction "1_1") (pintype "passive"))
      (node (ref "C42") (pin "2") (pinfunction "2_2") (pintype "passive"))
      (node (ref "C43") (pin "2") (pinfunction "2_2") (pintype "passive"))
      (node (ref "C48") (pin "2") (pinfunction "2_2") (pintype "passive"))
      (node (ref "C49") (pin "2") (pinfunction "2_2") (pintype "passive"))
      (node (ref "C50") (pin "2") (pinfunction "2_2") (pintype "passive"))
      (node (ref "C56") (pin "2") (pinfunction "2_2") (pintype "passive"))
      (node (ref "C8") (pin "2") (pinfunction "2_2") (pintype "passive"))
      (node (ref "FB2") (pin "1") (pinfunction "1_1") (pintype "passive"))
      (node (ref "J1") (pin "1") (pinfunction "1_1") (pintype "passive"))
      (node (ref "J2") (pin "4") (pinfunction "4_4") (pintype "passive"))
      (node (ref "P3") (pin "1") (pinfunction "1_1") (pintype "passive"))
      (node (ref "P3") (pin "5") (pinfunction "5_5") (pintype "passive"))
      (node (ref "P3") (pin "6") (pinfunction "6_6") (pintype "passive"))
      (node (ref "Q10") (pin "2") (pinfunction "E_2") (pintype "passive"))
      (node (ref "Q8") (pin "2") (pinfunction "E_2") (pintype "passive"))
      (node (ref "Q9") (pin "3") (pinfunction "C_3") (pintype "passive"))
      (node (ref "R38") (pin "1") (pinfunction "1_1") (pintype "passive"))
      (node (ref "R41") (pin "1") (pinfunction "1_1") (pintype "passive"))
      (node (ref "S1") (pin "2") (pinfunction "2_2") (pintype "passive"))
      (node (ref "S2") (pin "2") (pintype "passive"))
      (node (ref "TVS2") (pin "1") (pinfunction "1_1") (pintype "passive"))
      (node (ref "U10") (pin "4") (pinfunction "VSS_4") (pintype "passive"))
      (node (ref "U11") (pin "3") (pinfunction "GND_3") (pintype "passive"))
      (node (ref "U5") (pin "4") (pinfunction "GND_4") (pintype "passive"))
      (node (ref "U5") (pin "9") (pinfunction "Pad_9") (pintype "passive"))
      (node (ref "U6") (pin "3") (pinfunction "GND_3") (pintype "passive"))
      (node (ref "U7") (pin "3") (pinfunction "GND_3") (pintype "passive"))
      (node (ref "U9") (pin "63") (pinfunction "VSS(VSSA)_63") (pintype "passive"))
      (node (ref "U9") (pin "65") (pinfunction "VREFN_65") (pintype "passive"))
    )
    (net (code "63") (name "Net-(C58-Pad2)") (class "Default")
      (node (ref "C58") (pin "2") (pinfunction "2_2") (pintype "passive"))
      (node (ref "D20") (pin "2") (pinfunction "2_2") (pintype "passive"))
      (node (ref "D21") (pin "2") (pinfunction "2_2") (pintype "passive"))
      (node (ref "P3") (pin "4") (pinfunction "4_4") (pintype "passive"))
      (node (ref "R") (pin "1") (pinfunction "1_1") (pintype "passive"))
      (node (ref "R83") (pin "2") (pinfunction "2_2") (pintype "passive"))
      (node (ref "R87") (pin "1") (pinfunction "1_1") (pintype "passive"))
      (node (ref "TVS1") (pin "1") (pinfunction "1_1") (pintype "passive"))
    )
    (net (code "64") (name "Net-(D5-K)") (class "Default")
      (node (ref "D5") (pin "2") (pinfunction "K_2") (pintype "passive"))
      (node (ref "R35") (pin "2") (pinfunction "2_2") (pintype "passive"))
    )
    (net (code "65") (name "Net-(D6-A)") (class "Default")
      (node (ref "D6") (pin "1") (pinfunction "A_1") (pintype "passive"))
      (node (ref "R39") (pin "2") (pinfunction "2_2") (pintype "passive"))
    )
    (net (code "66") (name "Net-(D10-A-Pad1)") (class "Default")
      (node (ref "D10") (pin "1") (pinfunction "A_1") (pintype "passive"))
      (node (ref "D10") (pin "2") (pinfunction "A_2") (pintype "passive"))
      (node (ref "FB1") (pin "2") (pinfunction "2_2") (pintype "passive"))
    )
    (net (code "67") (name "Net-(D10-C)") (class "Default")
      (node (ref "119") (pin "1") (pinfunction "1_1") (pintype "passive"))
      (node (ref "D10") (pin "3") (pinfunction "C_3") (pintype "passive"))
      (node (ref "P2") (pin "2") (pinfunction "2_2") (pintype "passive"))
      (node (ref "TVS2") (pin "2") (pinfunction "2_2") (pintype "passive"))
    )
    (net (code "68") (name "Net-(FB2-Pad2)") (class "Default")
      (node (ref "FB2") (pin "2") (pinfunction "2_2") (pintype "passive"))
      (node (ref "P2") (pin "1") (pinfunction "1_1") (pintype "passive"))
    )
    (net (code "69") (name "Net-(J1-Pad2)") (class "Default")
      (node (ref "J1") (pin "2") (pinfunction "2_2") (pintype "passive"))
      (node (ref "R37") (pin "1") (pinfunction "1_1") (pintype "passive"))
    )
    (net (code "70") (name "Net-(J1-Pad3)") (class "Default")
      (node (ref "J1") (pin "3") (pinfunction "3_3") (pintype "passive"))
      (node (ref "R36") (pin "1") (pinfunction "1_1") (pintype "passive"))
    )
    (net (code "71") (name "Net-(J1-Pad4)") (class "Default")
      (node (ref "J1") (pin "4") (pinfunction "4_4") (pintype "passive"))
      (node (ref "R31") (pin "1") (pinfunction "1_1") (pintype "passive"))
    )
    (net (code "72") (name "Net-(J2-Pad1)") (class "Default")
      (node (ref "J2") (pin "1") (pinfunction "1_1") (pintype "passive"))
      (node (ref "R1") (pin "2") (pinfunction "2_2") (pintype "passive"))
    )
    (net (code "73") (name "Net-(Q7-B)") (class "Default")
      (node (ref "Q7") (pin "1") (pinfunction "B_1") (pintype "passive"))
      (node (ref "R27") (pin "2") (pinfunction "2_2") (pintype "passive"))
    )
    (net (code "74") (name "Net-(Q8-B)") (class "Default")
      (node (ref "Q8") (pin "1") (pinfunction "B_1") (pintype "passive"))
      (node (ref "R31") (pin "2") (pinfunction "2_2") (pintype "passive"))
      (node (ref "R38") (pin "2") (pinfunction "2_2") (pintype "passive"))
    )
    (net (code "75") (name "Net-(Q9-B)") (class "Default")
      (node (ref "Q9") (pin "1") (pinfunction "B_1") (pintype "passive"))
      (node (ref "R40") (pin "2") (pinfunction "2_2") (pintype "passive"))
    )
    (net (code "76") (name "Net-(Q9-E)") (class "Default")
      (node (ref "Q9") (pin "2") (pinfunction "E_2") (pintype "passive"))
      (node (ref "R35") (pin "1") (pinfunction "1_1") (pintype "passive"))
    )
    (net (code "77") (name "Net-(Q10-B)") (class "Default")
      (node (ref "C32") (pin "1") (pinfunction "1_1") (pintype "passive"))
      (node (ref "Q10") (pin "1") (pinfunction "B_1") (pintype "passive"))
      (node (ref "R39") (pin "1") (pinfunction "1_1") (pintype "passive"))
      (node (ref "R41") (pin "2") (pinfunction "2_2") (pintype "passive"))
    )
    (net (code "78") (name "Net-(Q12-B)") (class "Default")
      (node (ref "Q12") (pin "1") (pinfunction "B_1") (pintype "passive"))
      (node (ref "R49") (pin "2") (pinfunction "2_2") (pintype "passive"))
    )
    (net (code "79") (name "Net-(Q12-C)") (class "Default")
      (node (ref "C36") (pin "1") (pinfunction "1_1") (pintype "passive"))
      (node (ref "Q12") (pin "3") (pinfunction "C_3") (pintype "passive"))
      (node (ref "U10") (pin "7") (pinfunction "HOLD#_7") (pintype "passive"))
      (node (ref "U10") (pin "8") (pinfunction "VDD_8") (pintype "passive"))
    )
    (net (code "80") (name "Net-(U5-OUT1)") (class "Default")
      (node (ref "R83") (pin "1") (pinfunction "1_1") (pintype "passive"))
      (node (ref "R87") (pin "2") (pinfunction "2_2") (pintype "passive"))
      (node (ref "U5") (pin "2") (pinfunction "OUT1_2") (pintype "passive"))
    )
    (net (code "81") (name "Net-(U5-OUT2)") (class "Default")
      (node (ref "B") (pin "1") (pinfunction "1_1") (pintype "passive"))
      (node (ref "C58") (pin "1") (pinfunction "1_1") (pintype "passive"))
      (node (ref "D20") (pin "1") (pinfunction "1_1") (pintype "passive"))
      (node (ref "D21") (pin "1") (pinfunction "1_1") (pintype "passive"))
      (node (ref "P3") (pin "3") (pinfunction "3_3") (pintype "passive"))
      (node (ref "TVS1") (pin "2") (pinfunction "2_2") (pintype "passive"))
      (node (ref "U5") (pin "3") (pinfunction "OUT2_3") (pintype "passive"))
    )
    (net (code "82") (name "Net-(U9-VDD15)") (class "Default")
      (node (ref "C38") (pin "1") (pinfunction "1_1") (pintype "passive"))
      (node (ref "U9") (pin "62") (pinfunction "VDD15_62") (pintype "passive"))
    )
    (net (code "83") (name "unconnected-(U9-PA15{slash}WKUP0{slash}SVS{slash}COMP3_OUT-Pad5)") (class "Default")
      (node (ref "U9") (pin "5") (pinfunction "PA15/WKUP0/SVS/COMP3_OUT_5") (pintype "passive"))
    )
    (net (code "84") (name "unconnected-(U9-PC1{slash}VDISP3{slash}GPT1_CH2{slash}COMP3_INP2{slash}LUT1_OUT-Pad47)") (class "Default")
      (node (ref "U9") (pin "47") (pinfunction "PC1/VDISP3/GPT1_CH2/COMP3_INP2/LUT1_OUT_47") (pintype "passive"))
    )
    (net (code "85") (name "unconnected-(U9-PC4{slash}SEG13{slash}UART5_RX{slash}COMP1_OUT{slash}OPA1_OUT2-Pad50)") (class "Default")
      (node (ref "U9") (pin "50") (pinfunction "PC4/SEG13/UART5_RX/COMP1_OUT/OPA1_OUT2_50") (pintype "passive"))
    )
    (net (code "86") (name "unconnected-(U9-PC8{slash}SEG17{slash}ADC_IN13{slash}SPI2_SCK-Pad54)") (class "Default")
      (node (ref "U9") (pin "54") (pinfunction "PC8/SEG17/ADC_IN13/SPI2_SCK_54") (pintype "passive"))
    )
    (net (code "87") (name "unconnected-(U9-PC11{slash}SEG20{slash}U7816CLK{slash}GPTO_CH3{slash}ADC_IN16-Pad57)") (class "Default")
      (node (ref "U9") (pin "57") (pinfunction "PC11/SEG20/U7816CLK/GPTO_CH3/ADC_IN16_57") (pintype "passive"))
    )
    (net (code "88") (name "unconnected-(U9-PC12{slash}SEG21{slash}U7816IO{slash}GPTO_CH4{slash}ADC_IN17-Pad58)") (class "Default")
      (node (ref "U9") (pin "58") (pinfunction "PC12/SEG21/U7816IO/GPTO_CH4/ADC_IN17_58") (pintype "passive"))
    )
    (net (code "89") (name "unconnected-(U9-PC13{slash}SEG40{slash}U7816CLK{slash}LPT16_CH1-Pad40)") (class "Default")
      (node (ref "U9") (pin "40") (pinfunction "PC13/SEG40/U7816CLK/LPT16_CH1_40") (pintype "passive"))
    )
    (net (code "90") (name "unconnected-(U9-PC14{slash}SEG41{slash}U7816IO{slash}LPT16_CH2-Pad41)") (class "Default")
      (node (ref "U9") (pin "41") (pinfunction "PC14/SEG41/U7816IO/LPT16_CH2_41") (pintype "passive"))
    )
    (net (code "91") (name "unconnected-(U9-PD0{slash}SEG22{slash}UART5_RX{slash}ADC_IN7{slash}GPT2_CH1-Pad71)") (class "Default")
      (node (ref "U9") (pin "71") (pinfunction "PD0/SEG22/UART5_RX/ADC_IN7/GPT2_CH1_71") (pintype "passive"))
    )
    (net (code "92") (name "unconnected-(U9-PD1{slash}SEG23{slash}UART5_TX{slash}ADC_IN1{slash}GPT2_CH2-Pad72)") (class "Default")
      (node (ref "U9") (pin "72") (pinfunction "PD1/SEG23/UART5_TX/ADC_IN1/GPT2_CH2_72") (pintype "passive"))
    )
    (net (code "93") (name "unconnected-(U9-PD2{slash}SEG24{slash}SPI1_SSN{slash}ADC_IN8{slash}GPT2_CH3-Pad73)") (class "Default")
      (node (ref "U9") (pin "73") (pinfunction "PD2/SEG24/SPI1_SSN/ADC_IN8/GPT2_CH3_73") (pintype "passive"))
    )
    (net (code "94") (name "unconnected-(U9-PD3{slash}SEG25{slash}SPI1_SCK{slash}ADC_IN2{slash}GPT2_CH4-Pad74)") (class "Default")
      (node (ref "U9") (pin "74") (pinfunction "PD3/SEG25/SPI1_SCK/ADC_IN2/GPT2_CH4_74") (pintype "passive"))
    )
    (net (code "95") (name "unconnected-(U9-PD4{slash}SEG26{slash}SPI1_MISO{slash}ADC_IN9{slash}GPT2_ETR-Pad75)") (class "Default")
      (node (ref "U9") (pin "75") (pinfunction "PD4/SEG26/SPI1_MISO/ADC_IN9/GPT2_ETR_75") (pintype "passive"))
    )
    (net (code "96") (name "unconnected-(U9-PD10{slash}CAN_RX{slash}ADC_IN18-Pad1)") (class "Default")
      (node (ref "U9") (pin "1") (pinfunction "PD10/CAN_RX/ADC_IN18_1") (pintype "passive"))
    )
    (net (code "97") (name "unconnected-(U9-PD11(WKUP6){slash}FOUT0{slash}ADC_IN0{slash}ATIM_BRK1-Pad70)") (class "Default")
      (node (ref "U9") (pin "70") (pinfunction "PD11(WKUP6)/FOUT0/ADC_IN0/ATIM_BRK1_70") (pintype "passive"))
    )
    (net (code "98") (name "unconnected-(U9-PE8-Pad20)") (class "Default")
      (node (ref "U9") (pin "20") (pinfunction "PE8_20") (pintype "passive"))
    )
  )
)
